# Sensor-RGB.net
KiCad netlist of a schematic drawn in Altium Designer
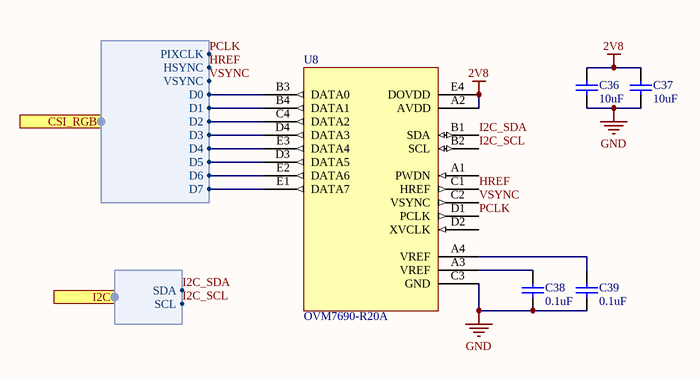
[diagram p0: Sensor-RGB.SchDoc]

(export (version "E")
  (design (tool "Eeschema 10.0.6"))
  (components
    (comp (ref "C36")
      (value "10uF")
      (footprint "C0402[1005X55]")
      (description "10uF 6.3V 20% 0402 (1005 Metric)")
      (fields (field (name "PARTNUMBER") "GRM155R60J106ME44D") (field (name "MANUFACTURER") "Murata"))
      (libsource (lib "Capacitors") (part "CAP_10uF_6.3V_0402_20%"))
    )
    (comp (ref "C37")
      (value "10uF")
      (footprint "C0402[1005X55]")
      (description "10uF 6.3V 20% 0402 (1005 Metric)")
      (fields (field (name "PARTNUMBER") "GRM155R60J106ME44D") (field (name "MANUFACTURER") "Murata"))
      (libsource (lib "Capacitors") (part "CAP_10uF_6.3V_0402_20%"))
    )
    (comp (ref "C38")
      (value "0.1uF")
      (footprint "C0201[0603X30]")
      (description "0.1uF 6.3V 10% 0201 (0603 Metric)")
      (fields (field (name "PARTNUMBER") "GRT033R60J104KE01D") (field (name "MANUFACTURER") "Murata"))
      (libsource (lib "Capacitors") (part "CAP_0.1uF_6.3V_0201_10%"))
    )
    (comp (ref "C39")
      (value "0.1uF")
      (footprint "C0201[0603X30]")
      (description "0.1uF 6.3V 10% 0201 (0603 Metric)")
      (fields (field (name "PARTNUMBER") "GRT033R60J104KE01D") (field (name "MANUFACTURER") "Murata"))
      (libsource (lib "Capacitors") (part "CAP_0.1uF_6.3V_0201_10%"))
    )
    (comp (ref "U8")
      (value "OVM7690-R20A")
      (description "SENSOR CAMERA CMOS 20CAMERACUBE")
      (fields (field (name "MANUFACTURER") "OmniVision Technologies"))
      (libsource (lib "ICs") (part "OVM7690-R20A"))
    )
  )
  (nets
    (net (code "3") (name "/D0") (class "Default")
      (node (ref "U8") (pin "B3") (pinfunction "DATA0_B3") (pintype "output"))
    )
    (net (code "4") (name "/D1") (class "Default")
      (node (ref "U8") (pin "B4") (pinfunction "DATA1_B4") (pintype "output"))
    )
    (net (code "5") (name "/D2") (class "Default")
      (node (ref "U8") (pin "C4") (pinfunction "DATA2_C4") (pintype "output"))
    )
    (net (code "6") (name "/D3") (class "Default")
      (node (ref "U8") (pin "D4") (pinfunction "DATA3_D4") (pintype "output"))
    )
    (net (code "7") (name "/D4") (class "Default")
      (node (ref "U8") (pin "E3") (pinfunction "DATA4_E3") (pintype "output"))
    )
    (net (code "8") (name "/D5") (class "Default")
      (node (ref "U8") (pin "D3") (pinfunction "DATA5_D3") (pintype "output"))
    )
    (net (code "9") (name "/D6") (class "Default")
      (node (ref "U8") (pin "E2") (pinfunction "DATA6_E2") (pintype "output"))
    )
    (net (code "10") (name "/D7") (class "Default")
      (node (ref "U8") (pin "E1") (pinfunction "DATA7_E1") (pintype "output"))
    )
    (net (code "11") (name "/HREF") (class "Default")
      (node (ref "U8") (pin "C1") (pinfunction "HREF_C1") (pintype "output"))
    )
    (net (code "12") (name "/I2C_SCL") (class "Default")
      (node (ref "U8") (pin "B2") (pinfunction "SCL_B2") (pintype "bidirectional"))
    )
    (net (code "13") (name "/I2C_SDA") (class "Default")
      (node (ref "U8") (pin "B1") (pinfunction "SDA_B1") (pintype "bidirectional"))
    )
    (net (code "14") (name "/PCLK") (class "Default")
      (node (ref "U8") (pin "D1") (pinfunction "PCLK_D1") (pintype "output"))
    )
    (net (code "15") (name "/VSYNC") (class "Default")
      (node (ref "U8") (pin "C2") (pinfunction "VSYNC_C2") (pintype "output"))
    )
    (net (code "18") (name "2V8") (class "Default")
      (node (ref "C36") (pin "2") (pinfunction "2_2") (pintype "passive"))
      (node (ref "C37") (pin "2") (pinfunction "2_2") (pintype "passive"))
      (node (ref "U8") (pin "A2") (pinfunction "AVDD_A2") (pintype "power_in"))
      (node (ref "U8") (pin "E4") (pinfunction "DOVDD_E4") (pintype "power_in"))
    )
    (net (code "19") (name "GND") (class "Default")
      (node (ref "C36") (pin "1") (pinfunction "1_1") (pintype "passive"))
      (node (ref "C37") (pin "1") (pinfunction "1_1") (pintype "passive"))
      (node (ref "C38") (pin "1") (pinfunction "1_1") (pintype "passive"))
      (node (ref "C39") (pin "1") (pinfunction "1_1") (pintype "passive"))
      (node (ref "U8") (pin "C3") (pinfunction "GND_C3") (pintype "power_in"))
    )
    (net (code "20") (name "Net-(C38-Pad2)") (class "Default")
      (node (ref "C38") (pin "2") (pinfunction "2_2") (pintype "passive"))
      (node (ref "U8") (pin "A3") (pinfunction "VREF_A3") (pintype "power_in"))
    )
    (net (code "21") (name "Net-(C39-Pad2)") (class "Default")
      (node (ref "C39") (pin "2") (pinfunction "2_2") (pintype "passive"))
      (node (ref "U8") (pin "A4") (pinfunction "VREF_A4") (pintype "power_in"))
    )
    (net (code "22") (name "unconnected-(U8-PWDN-PadA1)") (class "Default")
      (node (ref "U8") (pin "A1") (pinfunction "PWDN_A1") (pintype "input"))
    )
    (net (code "23") (name "unconnected-(U8-XVCLK-PadD2)") (class "Default")
      (node (ref "U8") (pin "D2") (pinfunction "XVCLK_D2") (pintype "input"))
    )
  )
)
